# ELEC-DEM-555Timer.net
KiCad netlist of a schematic drawn in Altium Designer
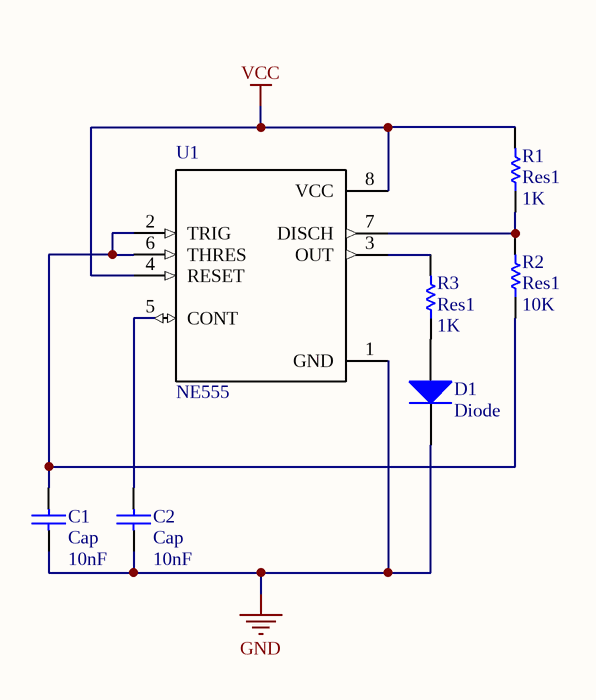
[diagram p0: ELEC-DEM-555Timer.SchDoc]

(export (version "E")
  (design (tool "Eeschema 10.0.6"))
  (components
    (comp (ref "C1")
      (value "Cap")
      (footprint "RAD-0.3")
      (description "Capacitor")
      (fields (field (name "ALTIUM_VALUE") "10nF") (field (name "PUBLISHER") "Altium Limited"))
      (libsource (lib "Miscellaneous Devices") (part "Cap"))
    )
    (comp (ref "C2")
      (value "Cap")
      (footprint "RAD-0.3")
      (description "Capacitor")
      (fields (field (name "ALTIUM_VALUE") "10nF") (field (name "PUBLISHER") "Altium Limited"))
      (libsource (lib "Miscellaneous Devices") (part "Cap"))
    )
    (comp (ref "D1")
      (value "Diode")
      (footprint "SMC")
      (description "Default Diode")
      (fields (field (name "PUBLISHER") "Altium Limited"))
      (libsource (lib "Miscellaneous Devices") (part "Diode"))
    )
    (comp (ref "R1")
      (value "Res1")
      (footprint "AXIAL-0.3")
      (description "Resistor")
      (fields (field (name "ALTIUM_VALUE") "1K") (field (name "PUBLISHER") "Altium Limited"))
      (libsource (lib "Miscellaneous Devices") (part "Res1"))
    )
    (comp (ref "R2")
      (value "Res1")
      (footprint "AXIAL-0.3")
      (description "Resistor")
      (fields (field (name "ALTIUM_VALUE") "10K") (field (name "PUBLISHER") "Altium Limited"))
      (libsource (lib "Miscellaneous Devices") (part "Res1"))
    )
    (comp (ref "R3")
      (value "Res1")
      (footprint "AXIAL-0.3")
      (description "Resistor")
      (fields (field (name "ALTIUM_VALUE") "1K") (field (name "PUBLISHER") "Altium Limited"))
      (libsource (lib "Miscellaneous Devices") (part "Res1"))
    )
    (comp (ref "U1")
      (value "NE555")
      (footprint "DIP794W45P254L1060H508Q8")
      (fields (field (name "MF") "MCM Electronics"))
      (libsource (lib "NE555") (part "NE555"))
    )
  )
  (nets
    (net (code "1") (name "GND") (class "Default")
      (node (ref "C1") (pin "1") (pinfunction "1_1") (pintype "passive"))
      (node (ref "C2") (pin "1") (pinfunction "1_1") (pintype "passive"))
      (node (ref "D1") (pin "2") (pinfunction "K_2") (pintype "passive"))
      (node (ref "U1") (pin "1") (pinfunction "GND_1") (pintype "power_in"))
    )
    (net (code "2") (name "Net-(D1-A)") (class "Default")
      (node (ref "D1") (pin "1") (pinfunction "A_1") (pintype "passive"))
      (node (ref "R3") (pin "1") (pinfunction "1_1") (pintype "passive"))
    )
    (net (code "3") (name "Net-(U1-CONT)") (class "Default")
      (node (ref "C2") (pin "2") (pinfunction "2_2") (pintype "passive"))
      (node (ref "U1") (pin "5") (pinfunction "CONT_5") (pintype "bidirectional"))
    )
    (net (code "4") (name "Net-(U1-DISCH)") (class "Default")
      (node (ref "R1") (pin "1") (pinfunction "1_1") (pintype "passive"))
      (node (ref "R2") (pin "2") (pinfunction "2_2") (pintype "passive"))
      (node (ref "U1") (pin "7") (pinfunction "DISCH_7") (pintype "output"))
    )
    (net (code "5") (name "Net-(U1-OUT)") (class "Default")
      (node (ref "R3") (pin "2") (pinfunction "2_2") (pintype "passive"))
      (node (ref "U1") (pin "3") (pinfunction "OUT_3") (pintype "output"))
    )
    (net (code "6") (name "Net-(U1-THRES)") (class "Default")
      (node (ref "C1") (pin "2") (pinfunction "2_2") (pintype "passive"))
      (node (ref "R2") (pin "1") (pinfunction "1_1") (pintype "passive"))
      (node (ref "U1") (pin "2") (pinfunction "TRIG_2") (pintype "input"))
      (node (ref "U1") (pin "6") (pinfunction "THRES_6") (pintype "input"))
    )
    (net (code "7") (name "VCC") (class "Default")
      (node (ref "R1") (pin "2") (pinfunction "2_2") (pintype "passive"))
      (node (ref "U1") (pin "4") (pinfunction "RESET_4") (pintype "input"))
      (node (ref "U1") (pin "8") (pinfunction "VCC_8") (pintype "power_in"))
    )
  )
)
